# Keyboard.net
KiCad netlist of a schematic drawn in EAGLE
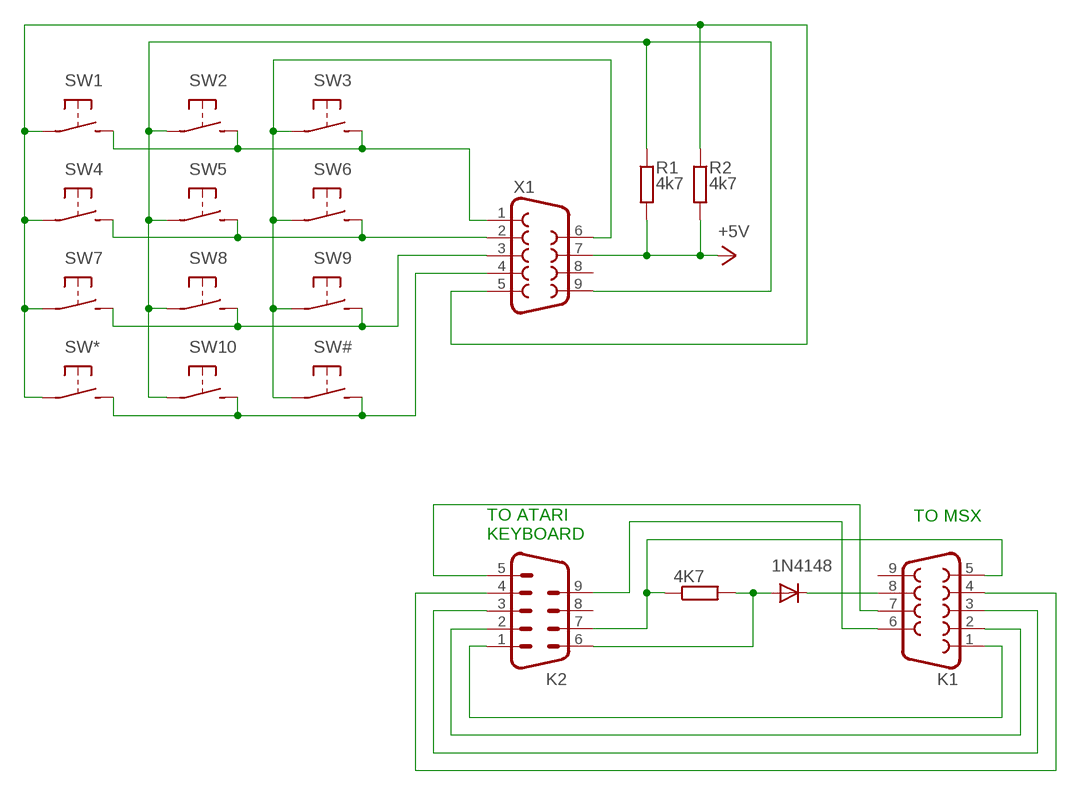
[diagram p0: schematic, sheet 1]

(export (version "E")
  (design (tool "Eeschema 10.0.6"))
  (components
    (comp (ref "1N4148")
      (value "DIODE-D-5")
      (footprint "eagle-import:D-5")
      (libsource (lib "eagle-import") (part "DIODE-D-5"))
    )
    (comp (ref "4K7")
      (value "R-EU_0204/5")
      (footprint "eagle-import:0204_5")
      (libsource (lib "eagle-import") (part "R-EU_0204/5"))
    )
    (comp (ref "K1")
      (value "F09D")
      (footprint "eagle-import:F09D")
      (libsource (lib "eagle-import") (part "F09D"))
    )
    (comp (ref "K2")
      (value "M09D")
      (footprint "eagle-import:M09D")
      (libsource (lib "eagle-import") (part "M09D"))
    )
    (comp (ref "R1")
      (value "4k7")
      (footprint "eagle-import:0204_7")
      (libsource (lib "eagle-import") (part "R-EU_0204/7"))
    )
    (comp (ref "R2")
      (value "4k7")
      (footprint "eagle-import:0204_7")
      (libsource (lib "eagle-import") (part "R-EU_0204/7"))
    )
    (comp (ref "SW#")
      (value "MINISPDT")
      (footprint "eagle-import:2PST_MINI")
      (libsource (lib "eagle-import") (part "MINISPDT"))
    )
    (comp (ref "SW*")
      (value "MINISPDT")
      (footprint "eagle-import:2PST_MINI")
      (libsource (lib "eagle-import") (part "MINISPDT"))
    )
    (comp (ref "SW1")
      (value "MINISPDT")
      (footprint "eagle-import:2PST_MINI")
      (libsource (lib "eagle-import") (part "MINISPDT"))
    )
    (comp (ref "SW2")
      (value "MINISPDT")
      (footprint "eagle-import:2PST_MINI")
      (libsource (lib "eagle-import") (part "MINISPDT"))
    )
    (comp (ref "SW3")
      (value "MINISPDT")
      (footprint "eagle-import:2PST_MINI")
      (libsource (lib "eagle-import") (part "MINISPDT"))
    )
    (comp (ref "SW4")
      (value "MINISPDT")
      (footprint "eagle-import:2PST_MINI")
      (libsource (lib "eagle-import") (part "MINISPDT"))
    )
    (comp (ref "SW5")
      (value "MINISPDT")
      (footprint "eagle-import:2PST_MINI")
      (libsource (lib "eagle-import") (part "MINISPDT"))
    )
    (comp (ref "SW6")
      (value "MINISPDT")
      (footprint "eagle-import:2PST_MINI")
      (libsource (lib "eagle-import") (part "MINISPDT"))
    )
    (comp (ref "SW7")
      (value "MINISPDT")
      (footprint "eagle-import:2PST_MINI")
      (libsource (lib "eagle-import") (part "MINISPDT"))
    )
    (comp (ref "SW8")
      (value "MINISPDT")
      (footprint "eagle-import:2PST_MINI")
      (libsource (lib "eagle-import") (part "MINISPDT"))
    )
    (comp (ref "SW9")
      (value "MINISPDT")
      (footprint "eagle-import:2PST_MINI")
      (libsource (lib "eagle-import") (part "MINISPDT"))
    )
    (comp (ref "SW10")
      (value "MINISPDT")
      (footprint "eagle-import:2PST_MINI")
      (libsource (lib "eagle-import") (part "MINISPDT"))
    )
    (comp (ref "X1")
      (value "F09D")
      (footprint "eagle-import:F09D")
      (libsource (lib "eagle-import") (part "F09D"))
    )
  )
  (nets
    (net (code "1") (name "+5V") (class "Default")
      (node (ref "R1") (pin "2") (pinfunction "2_2") (pintype "passive"))
      (node (ref "R2") (pin "2") (pinfunction "2_2") (pintype "passive"))
      (node (ref "X1") (pin "7") (pinfunction "7_7") (pintype "passive"))
    )
    (net (code "2") (name "Net-(1N4148-PadA)") (class "Default")
      (node (ref "1N4148") (pin "A") (pinfunction "A_A") (pintype "passive"))
      (node (ref "4K7") (pin "2") (pinfunction "2_2") (pintype "passive"))
      (node (ref "K2") (pin "6") (pinfunction "6_6") (pintype "passive"))
    )
    (net (code "3") (name "Net-(1N4148-PadC)") (class "Default")
      (node (ref "1N4148") (pin "C") (pinfunction "C_C") (pintype "passive"))
      (node (ref "K1") (pin "8") (pinfunction "8_8") (pintype "passive"))
    )
    (net (code "4") (name "Net-(4K7-Pad1)") (class "Default")
      (node (ref "4K7") (pin "1") (pinfunction "1_1") (pintype "passive"))
      (node (ref "K1") (pin "5") (pinfunction "5_5") (pintype "passive"))
      (node (ref "K2") (pin "7") (pinfunction "7_7") (pintype "passive"))
    )
    (net (code "5") (name "Net-(K1-Pad1)") (class "Default")
      (node (ref "K1") (pin "1") (pinfunction "1_1") (pintype "passive"))
      (node (ref "K2") (pin "1") (pinfunction "1_1") (pintype "passive"))
    )
    (net (code "6") (name "Net-(K1-Pad2)") (class "Default")
      (node (ref "K1") (pin "2") (pinfunction "2_2") (pintype "passive"))
      (node (ref "K2") (pin "2") (pinfunction "2_2") (pintype "passive"))
    )
    (net (code "7") (name "Net-(K1-Pad3)") (class "Default")
      (node (ref "K1") (pin "3") (pinfunction "3_3") (pintype "passive"))
      (node (ref "K2") (pin "3") (pinfunction "3_3") (pintype "passive"))
    )
    (net (code "8") (name "Net-(K1-Pad4)") (class "Default")
      (node (ref "K1") (pin "4") (pinfunction "4_4") (pintype "passive"))
      (node (ref "K2") (pin "4") (pinfunction "4_4") (pintype "passive"))
    )
    (net (code "9") (name "Net-(K1-Pad6)") (class "Default")
      (node (ref "K1") (pin "6") (pinfunction "6_6") (pintype "passive"))
      (node (ref "K2") (pin "9") (pinfunction "9_9") (pintype "passive"))
    )
    (net (code "10") (name "Net-(K1-Pad7)") (class "Default")
      (node (ref "K1") (pin "7") (pinfunction "7_7") (pintype "passive"))
      (node (ref "K2") (pin "5") (pinfunction "5_5") (pintype "passive"))
    )
    (net (code "11") (name "Net-(SW#-P)") (class "Default")
      (node (ref "SW#") (pin "P$1") (pinfunction "P_P$1") (pintype "passive"))
      (node (ref "SW3") (pin "P$1") (pinfunction "P_P$1") (pintype "passive"))
      (node (ref "SW6") (pin "P$1") (pinfunction "P_P$1") (pintype "passive"))
      (node (ref "SW9") (pin "P$1") (pinfunction "P_P$1") (pintype "passive"))
      (node (ref "X1") (pin "6") (pinfunction "6_6") (pintype "passive"))
    )
    (net (code "12") (name "Net-(SW#-S)") (class "Default")
      (node (ref "SW#") (pin "P$2") (pinfunction "S_P$2") (pintype "passive"))
      (node (ref "SW*") (pin "P$2") (pinfunction "S_P$2") (pintype "passive"))
      (node (ref "SW10") (pin "P$2") (pinfunction "S_P$2") (pintype "passive"))
      (node (ref "X1") (pin "4") (pinfunction "4_4") (pintype "passive"))
    )
    (net (code "13") (name "Net-(SW*-P)") (class "Default")
      (node (ref "R2") (pin "1") (pinfunction "1_1") (pintype "passive"))
      (node (ref "SW*") (pin "P$1") (pinfunction "P_P$1") (pintype "passive"))
      (node (ref "SW1") (pin "P$1") (pinfunction "P_P$1") (pintype "passive"))
      (node (ref "SW4") (pin "P$1") (pinfunction "P_P$1") (pintype "passive"))
      (node (ref "SW7") (pin "P$1") (pinfunction "P_P$1") (pintype "passive"))
      (node (ref "X1") (pin "5") (pinfunction "5_5") (pintype "passive"))
    )
    (net (code "14") (name "Net-(SW1-S)") (class "Default")
      (node (ref "SW1") (pin "P$2") (pinfunction "S_P$2") (pintype "passive"))
      (node (ref "SW2") (pin "P$2") (pinfunction "S_P$2") (pintype "passive"))
      (node (ref "SW3") (pin "P$2") (pinfunction "S_P$2") (pintype "passive"))
      (node (ref "X1") (pin "1") (pinfunction "1_1") (pintype "passive"))
    )
    (net (code "15") (name "Net-(SW4-S)") (class "Default")
      (node (ref "SW4") (pin "P$2") (pinfunction "S_P$2") (pintype "passive"))
      (node (ref "SW5") (pin "P$2") (pinfunction "S_P$2") (pintype "passive"))
      (node (ref "SW6") (pin "P$2") (pinfunction "S_P$2") (pintype "passive"))
      (node (ref "X1") (pin "2") (pinfunction "2_2") (pintype "passive"))
    )
    (net (code "16") (name "Net-(SW7-S)") (class "Default")
      (node (ref "SW7") (pin "P$2") (pinfunction "S_P$2") (pintype "passive"))
      (node (ref "SW8") (pin "P$2") (pinfunction "S_P$2") (pintype "passive"))
      (node (ref "SW9") (pin "P$2") (pinfunction "S_P$2") (pintype "passive"))
      (node (ref "X1") (pin "3") (pinfunction "3_3") (pintype "passive"))
    )
    (net (code "17") (name "Net-(SW10-P)") (class "Default")
      (node (ref "R1") (pin "1") (pinfunction "1_1") (pintype "passive"))
      (node (ref "SW10") (pin "P$1") (pinfunction "P_P$1") (pintype "passive"))
      (node (ref "SW2") (pin "P$1") (pinfunction "P_P$1") (pintype "passive"))
      (node (ref "SW5") (pin "P$1") (pinfunction "P_P$1") (pintype "passive"))
      (node (ref "SW8") (pin "P$1") (pinfunction "P_P$1") (pintype "passive"))
      (node (ref "X1") (pin "9") (pinfunction "9_9") (pintype "passive"))
    )
    (net (code "18") (name "unconnected-(K1-Pad9)") (class "Default")
      (node (ref "K1") (pin "9") (pinfunction "9_9") (pintype "passive"))
    )
    (net (code "19") (name "unconnected-(K2-Pad8)") (class "Default")
      (node (ref "K2") (pin "8") (pinfunction "8_8") (pintype "passive"))
    )
    (net (code "20") (name "unconnected-(X1-Pad8)") (class "Default")
      (node (ref "X1") (pin "8") (pinfunction "8_8") (pintype "passive"))
    )
  )
)
